# Schemetic_2.net
KiCad netlist of a schematic drawn in Altium Designer
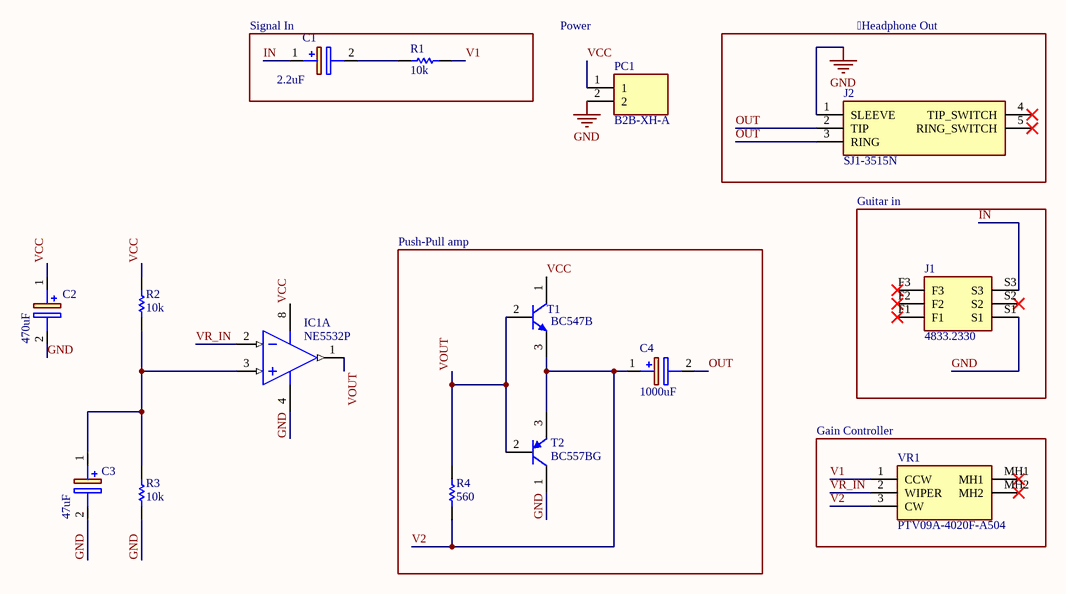
[diagram p0: Schemetic_2.SchDoc]

(export (version "E")
  (design (tool "Eeschema 10.0.6"))
  (components
    (comp (ref "C1")
      (value "2.2uF")
      (footprint "SamacSys:CAPPRD200W50D500H1250")
      (description "Capacitor Polarised")
      (fields
        (field (name "MANUFACTURER_PART_NUMBER") "ESK225M050AC3KA")
        (field (name "MOUSER PART NUMBER") "80-ESK225M050AC3KA")
      )
      (libsource (lib "*") (part "ESK225M050AC3KA"))
    )
    (comp (ref "C2")
      (value "470uF")
      (footprint "SamacSys:CAPPRD500W65D1000H1700")
      (description "Capacitor Polarised")
      (fields
        (field (name "MANUFACTURER_PART_NUMBER") "ECA-1VM471B")
        (field (name "MOUSER PART NUMBER") "667-ECA-1VM471B")
      )
      (libsource (lib "*") (part "ECA-1VM471B"))
    )
    (comp (ref "C3")
      (value "47uF")
      (footprint "SamacSys:CAPPRD500W60D1300H2200")
      (description "Capacitor Polarised")
      (fields
        (field (name "MANUFACTURER_PART_NUMBER") "UCS2E470MHD1TO")
        (field (name "MOUSER PART NUMBER") "647-UCS2E470MHD1TO")
      )
      (libsource (lib "*") (part "UCS2E470MHD1TO"))
    )
    (comp (ref "C4")
      (value "1000uF")
      (footprint "SamacSys:CAPPRD750W85D1600H2200")
      (description "Capacitor Polarised")
      (fields
        (field (name "MANUFACTURER_PART_NUMBER") "EEU-FC1V102S")
        (field (name "MOUSER PART NUMBER") "667-EEU-FC1V102S")
      )
      (libsource (lib "*") (part "EEU-FC1V102S"))
    )
    (comp (ref "IC1")
      (value "NE5532P")
      (footprint "P0008A")
      (fields (field (name "MANUFACTURER") "Texas Instruments"))
      (libsource (lib "Altium Content Vault") (part "TI-AMP-D6-2-8_D"))
    )
    (comp (ref "J1")
      (value "4833.2330")
      (footprint "SamacSys:48332330")
      (description "Connector")
      (fields (field (name "MOUSER PART NUMBER") "693-4833.233"))
      (libsource (lib "*") (part "4833.2330"))
    )
    (comp (ref "J2")
      (value "SJ1-3515N")
      (footprint "SamacSys:SJ13515N")
      (description "Connector")
      (fields (field (name "MOUSER PART NUMBER") "490-SJ1-3515N"))
      (libsource (lib "*") (part "SJ1-3515N"))
    )
    (comp (ref "PC1")
      (value "B2B-XH-A")
      (footprint "SamacSys:SHDR2W64P0X250_1X2_740X575X700P")
      (description "Connector")
      (libsource (lib "*") (part "B2B-XH-A"))
    )
    (comp (ref "R1")
      (value "10k")
      (footprint "RESA60-630X240")
      (description "Axial Resistor, 10 KOhm, +/- 1%, 0.25 W, -55 to 155 degC, 2-Pin THD, RoHS, Bulk")
      (fields (field (name "TOLERANCE") "1%") (field (name "MANUFACTURER") "Yageo"))
      (libsource (lib "Altium Content Vault") (part "RES-2"))
    )
    (comp (ref "R2")
      (value "10k")
      (footprint "RESA60-630X240")
      (description "Axial Resistor, 10 KOhm, +/- 1%, 0.25 W, -55 to 155 degC, 2-Pin THD, RoHS, Bulk")
      (fields (field (name "TOLERANCE") "1%") (field (name "MANUFACTURER") "Yageo"))
      (libsource (lib "Altium Content Vault") (part "RES-2"))
    )
    (comp (ref "R3")
      (value "10k")
      (footprint "RESA60-630X240")
      (description "Axial Resistor, 10 KOhm, +/- 1%, 0.25 W, -55 to 155 degC, 2-Pin THD, RoHS, Bulk")
      (fields (field (name "TOLERANCE") "1%") (field (name "MANUFACTURER") "Yageo"))
      (libsource (lib "Altium Content Vault") (part "RES-2"))
    )
    (comp (ref "R4")
      (value "560")
      (footprint "RESA60-630X240")
      (description "Axial Resistor, 10 KOhm, +/- 1%, 0.25 W, -55 to 155 degC, 2-Pin THD, RoHS, Bulk")
      (fields (field (name "TOLERANCE") "1%") (field (name "MANUFACTURER") "Yageo"))
      (libsource (lib "Altium Content Vault") (part "RES-2"))
    )
    (comp (ref "T1")
      (value "BC547B")
      (footprint "ONSC-TO-92-3-29-11")
      (description "Amplifier Transistor, NPN Silicon, 3-Pin TO-92, Bulk Box")
      (fields (field (name "MANUFACTURER") "On Semiconductor"))
      (libsource (lib "Altium Content Vault") (part "ONSC-NPN-C1B2E3-3"))
    )
    (comp (ref "T2")
      (value "BC557BG")
      (footprint "ONSC-TO-92-3-29-11")
      (description "Amplifier Transistor, PNP Silicon, 3-Pin TO-92, Pb-Free, Bulk Box")
      (fields (field (name "MANUFACTURER") "On Semiconductor"))
      (libsource (lib "Altium Content Vault") (part "ONSC-PNP-C1B2E3-3"))
    )
    (comp (ref "VR1")
      (value "PTV09A-4020F-A504")
      (footprint "SamacSys:PTV09A4020FA504")
      (description "Variable Resistor")
      (fields (field (name "MOUSER PART NUMBER") "652-PTV09A-4020FA504"))
      (libsource (lib "*") (part "PTV09A-4020F-A504"))
    )
  )
  (nets
    (net (code "1") (name "/IN") (class "Default")
      (node (ref "C1") (pin "1") (pinfunction "+_1") (pintype "passive"))
      (node (ref "J1") (pin "S3") (pinfunction "S3_S3") (pintype "passive"))
    )
    (net (code "2") (name "/OUT") (class "Default")
      (node (ref "C4") (pin "2") (pinfunction "-_2") (pintype "passive"))
      (node (ref "J2") (pin "2") (pinfunction "TIP_2") (pintype "passive"))
      (node (ref "J2") (pin "3") (pinfunction "RING_3") (pintype "passive"))
    )
    (net (code "3") (name "/V1") (class "Default")
      (node (ref "R1") (pin "2") (pinfunction "2_2") (pintype "passive"))
      (node (ref "VR1") (pin "1") (pinfunction "CCW_1") (pintype "passive"))
    )
    (net (code "4") (name "/V2") (class "Default")
      (node (ref "C4") (pin "1") (pinfunction "+_1") (pintype "passive"))
      (node (ref "R4") (pin "1") (pinfunction "1_1") (pintype "passive"))
      (node (ref "T1") (pin "3") (pinfunction "E_3") (pintype "passive"))
      (node (ref "T2") (pin "3") (pinfunction "E_3") (pintype "passive"))
      (node (ref "VR1") (pin "3") (pinfunction "CW_3") (pintype "passive"))
    )
    (net (code "5") (name "/VCC") (class "Default")
      (node (ref "C2") (pin "1") (pinfunction "+_1") (pintype "passive"))
      (node (ref "IC1") (pin "8") (pinfunction "VCC+_8") (pintype "power_in"))
      (node (ref "PC1") (pin "1") (pinfunction "1_1") (pintype "passive"))
      (node (ref "R2") (pin "2") (pinfunction "2_2") (pintype "passive"))
      (node (ref "T1") (pin "1") (pinfunction "C_1") (pintype "passive"))
    )
    (net (code "6") (name "/VOUT") (class "Default")
      (node (ref "IC1") (pin "1") (pinfunction "OUT1_1") (pintype "output"))
      (node (ref "R4") (pin "2") (pinfunction "2_2") (pintype "passive"))
      (node (ref "T1") (pin "2") (pinfunction "B_2") (pintype "passive"))
      (node (ref "T2") (pin "2") (pinfunction "B_2") (pintype "passive"))
    )
    (net (code "7") (name "/VR_IN") (class "Default")
      (node (ref "IC1") (pin "2") (pinfunction "IN1-_2") (pintype "input"))
      (node (ref "VR1") (pin "2") (pinfunction "WIPER_2") (pintype "passive"))
    )
    (net (code "8") (name "GND") (class "Default")
      (node (ref "C2") (pin "2") (pinfunction "-_2") (pintype "passive"))
      (node (ref "C3") (pin "2") (pinfunction "-_2") (pintype "passive"))
      (node (ref "IC1") (pin "4") (pinfunction "VCC-_4") (pintype "power_in"))
      (node (ref "J1") (pin "S1") (pinfunction "S1_S1") (pintype "passive"))
      (node (ref "J2") (pin "1") (pinfunction "SLEEVE_1") (pintype "passive"))
      (node (ref "PC1") (pin "2") (pinfunction "2_2") (pintype "passive"))
      (node (ref "R3") (pin "1") (pinfunction "1_1") (pintype "passive"))
      (node (ref "T2") (pin "1") (pinfunction "C_1") (pintype "passive"))
    )
    (net (code "9") (name "Net-(C1--)") (class "Default")
      (node (ref "C1") (pin "2") (pinfunction "-_2") (pintype "passive"))
      (node (ref "R1") (pin "1") (pinfunction "1_1") (pintype "passive"))
    )
    (net (code "10") (name "Net-(C3-+)") (class "Default")
      (node (ref "C3") (pin "1") (pinfunction "+_1") (pintype "passive"))
      (node (ref "IC1") (pin "3") (pinfunction "IN1+_3") (pintype "input"))
      (node (ref "R2") (pin "1") (pinfunction "1_1") (pintype "passive"))
      (node (ref "R3") (pin "2") (pinfunction "2_2") (pintype "passive"))
    )
    (net (code "11") (name "unconnected-(J1-PadF1)") (class "Default")
      (node (ref "J1") (pin "F1") (pinfunction "F1_F1") (pintype "passive+no_connect"))
    )
    (net (code "12") (name "unconnected-(J1-PadF2)") (class "Default")
      (node (ref "J1") (pin "F2") (pinfunction "F2_F2") (pintype "passive+no_connect"))
    )
    (net (code "13") (name "unconnected-(J1-PadF3)") (class "Default")
      (node (ref "J1") (pin "F3") (pinfunction "F3_F3") (pintype "passive+no_connect"))
    )
    (net (code "14") (name "unconnected-(J1-PadS2)") (class "Default")
      (node (ref "J1") (pin "S2") (pinfunction "S2_S2") (pintype "passive+no_connect"))
    )
    (net (code "15") (name "unconnected-(J2-RING_SWITCH-Pad5)") (class "Default")
      (node (ref "J2") (pin "5") (pinfunction "RING_SWITCH_5") (pintype "passive+no_connect"))
    )
    (net (code "16") (name "unconnected-(J2-TIP_SWITCH-Pad4)") (class "Default")
      (node (ref "J2") (pin "4") (pinfunction "TIP_SWITCH_4") (pintype "passive+no_connect"))
    )
    (net (code "17") (name "unconnected-(VR1-PadMH1)") (class "Default")
      (node (ref "VR1") (pin "MH1") (pinfunction "MH1_MH1") (pintype "passive+no_connect"))
    )
    (net (code "18") (name "unconnected-(VR1-PadMH2)") (class "Default")
      (node (ref "VR1") (pin "MH2") (pinfunction "MH2_MH2") (pintype "passive+no_connect"))
    )
  )
)
